# necklace1206ledfinal1.net
KiCad netlist of a schematic drawn in EAGLE
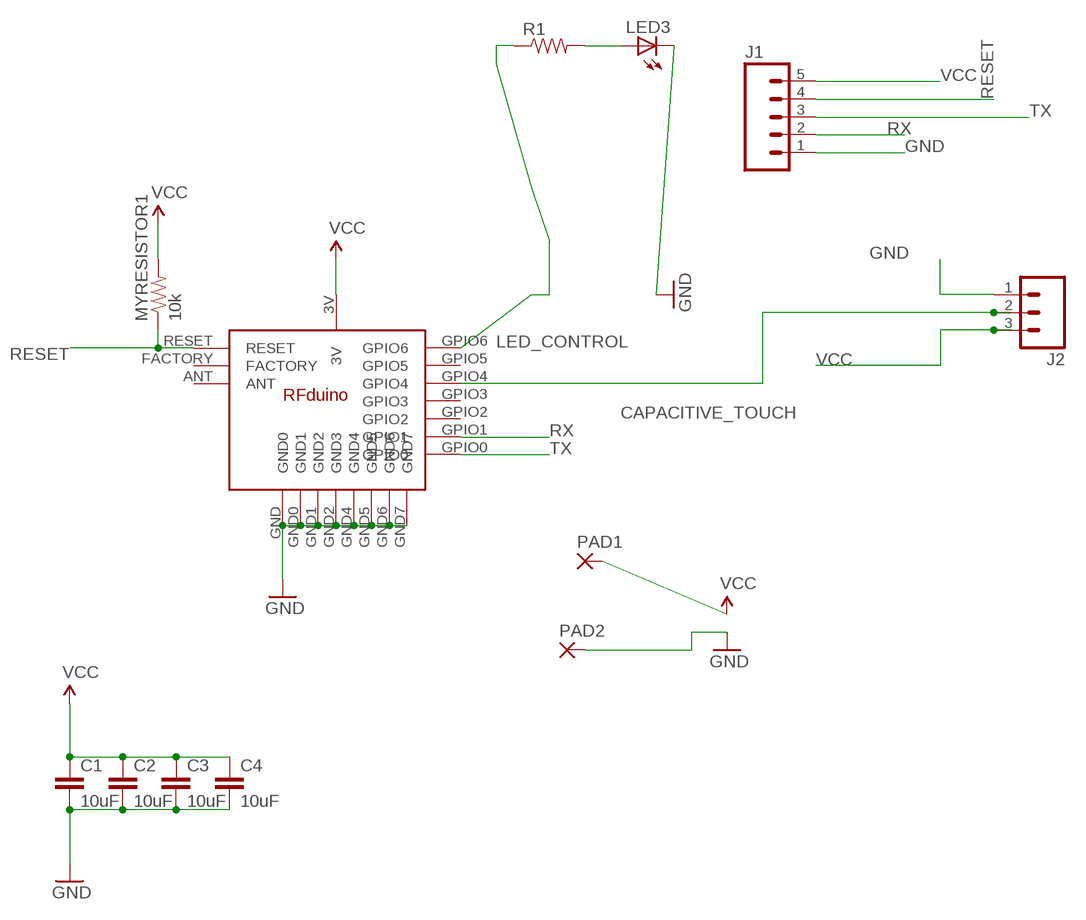
[diagram p0: schematic, sheet 1]

(export (version "E")
  (design (tool "Eeschema 10.0.6"))
  (components
    (comp (ref "C1")
      (value "10uF")
      (footprint "eagle-import:0603-CAP")
      (libsource (lib "eagle-import") (part "CAP0603-CAP"))
    )
    (comp (ref "C2")
      (value "10uF")
      (footprint "eagle-import:0603-CAP")
      (libsource (lib "eagle-import") (part "CAP0603-CAP"))
    )
    (comp (ref "C3")
      (value "10uF")
      (footprint "eagle-import:0603-CAP")
      (libsource (lib "eagle-import") (part "CAP0603-CAP"))
    )
    (comp (ref "C4")
      (value "10uF")
      (footprint "eagle-import:0603-CAP")
      (libsource (lib "eagle-import") (part "CAP0603-CAP"))
    )
    (comp (ref "J1")
      (value "M05PTH_LONGPADS")
      (footprint "eagle-import:1X05_LONGPADS")
      (libsource (lib "eagle-import") (part "M05PTH_LONGPADS"))
    )
    (comp (ref "J2")
      (value "M03LOCK_LONGPADS")
      (footprint "eagle-import:1X03_LOCK_LONGPADS")
      (libsource (lib "eagle-import") (part "M03LOCK_LONGPADS"))
    )
    (comp (ref "LED3")
      (value "LEDSMT1206")
      (footprint "eagle-import:1206")
      (libsource (lib "eagle-import") (part "LEDSMT1206"))
    )
    (comp (ref "MYRESISTOR1")
      (value "10k")
      (footprint "eagle-import:0603-RES")
      (libsource (lib "eagle-import") (part "RESISTOR0603-RES"))
    )
    (comp (ref "PAD1")
      (value "3,81/1,4")
      (footprint "eagle-import:3,81_1,4")
      (libsource (lib "eagle-import") (part "3,81/1,4"))
    )
    (comp (ref "PAD2")
      (value "3,81/1,4")
      (footprint "eagle-import:3,81_1,4")
      (libsource (lib "eagle-import") (part "3,81/1,4"))
    )
    (comp (ref "R1")
      (value "RESISTOR0603")
      (footprint "eagle-import:0603-RES")
      (libsource (lib "eagle-import") (part "RESISTOR0603"))
    )
    (comp (ref "U$2")
      (value "RFDUINO")
      (footprint "eagle-import:RFDUINO")
      (libsource (lib "eagle-import") (part "RFDUINO"))
    )
  )
  (nets
    (net (code "1") (name "/CAPACITIVE_TOUCH") (class "Default")
      (node (ref "J2") (pin "2") (pinfunction "2_2") (pintype "passive"))
      (node (ref "U$2") (pin "GPIO4") (pinfunction "GPIO4_GPIO4") (pintype "bidirectional"))
    )
    (net (code "2") (name "/LED_CONTROL") (class "Default")
      (node (ref "R1") (pin "1") (pinfunction "1_1") (pintype "passive"))
      (node (ref "U$2") (pin "GPIO6") (pinfunction "GPIO6_GPIO6") (pintype "bidirectional"))
    )
    (net (code "3") (name "/RESET") (class "Default")
      (node (ref "J1") (pin "4") (pinfunction "4_4") (pintype "passive"))
      (node (ref "MYRESISTOR1") (pin "1") (pinfunction "1_1") (pintype "passive"))
      (node (ref "U$2") (pin "RESET") (pinfunction "RESET_RESET") (pintype "bidirectional"))
    )
    (net (code "4") (name "/RX") (class "Default")
      (node (ref "J1") (pin "2") (pinfunction "2_2") (pintype "passive"))
      (node (ref "U$2") (pin "GPIO1") (pinfunction "GPIO1_GPIO1") (pintype "bidirectional"))
    )
    (net (code "5") (name "/TX") (class "Default")
      (node (ref "J1") (pin "3") (pinfunction "3_3") (pintype "passive"))
      (node (ref "U$2") (pin "GPIO0") (pinfunction "GPIO0_GPIO0") (pintype "bidirectional"))
    )
    (net (code "6") (name "GND") (class "Default")
      (node (ref "C1") (pin "2") (pinfunction "2_2") (pintype "passive"))
      (node (ref "C2") (pin "2") (pinfunction "2_2") (pintype "passive"))
      (node (ref "C3") (pin "2") (pinfunction "2_2") (pintype "passive"))
      (node (ref "C4") (pin "2") (pinfunction "2_2") (pintype "passive"))
      (node (ref "J1") (pin "1") (pinfunction "1_1") (pintype "passive"))
      (node (ref "J2") (pin "1") (pinfunction "1_1") (pintype "passive"))
      (node (ref "LED3") (pin "C") (pinfunction "C_C") (pintype "passive"))
      (node (ref "PAD2") (pin "1") (pinfunction "P_1") (pintype "passive"))
      (node (ref "U$2") (pin "GND") (pinfunction "GND0_GND") (pintype "bidirectional"))
      (node (ref "U$2") (pin "GND0") (pinfunction "GND1_GND0") (pintype "bidirectional"))
      (node (ref "U$2") (pin "GND1") (pinfunction "GND2_GND1") (pintype "bidirectional"))
      (node (ref "U$2") (pin "GND2") (pinfunction "GND3_GND2") (pintype "bidirectional"))
      (node (ref "U$2") (pin "GND4") (pinfunction "GND4_GND4") (pintype "bidirectional"))
      (node (ref "U$2") (pin "GND5") (pinfunction "GND5_GND5") (pintype "bidirectional"))
      (node (ref "U$2") (pin "GND6") (pinfunction "GND6_GND6") (pintype "bidirectional"))
      (node (ref "U$2") (pin "GND7") (pinfunction "GND7_GND7") (pintype "bidirectional"))
    )
    (net (code "7") (name "Net-(LED3-PadA)") (class "Default")
      (node (ref "LED3") (pin "A") (pinfunction "A_A") (pintype "passive"))
      (node (ref "R1") (pin "2") (pinfunction "2_2") (pintype "passive"))
    )
    (net (code "8") (name "VCC") (class "Default")
      (node (ref "C1") (pin "1") (pinfunction "1_1") (pintype "passive"))
      (node (ref "C2") (pin "1") (pinfunction "1_1") (pintype "passive"))
      (node (ref "C3") (pin "1") (pinfunction "1_1") (pintype "passive"))
      (node (ref "C4") (pin "1") (pinfunction "1_1") (pintype "passive"))
      (node (ref "J1") (pin "5") (pinfunction "5_5") (pintype "passive"))
      (node (ref "J2") (pin "3") (pinfunction "3_3") (pintype "passive"))
      (node (ref "MYRESISTOR1") (pin "2") (pinfunction "2_2") (pintype "passive"))
      (node (ref "PAD1") (pin "1") (pinfunction "P_1") (pintype "passive"))
      (node (ref "U$2") (pin "3V") (pinfunction "3V_3V") (pintype "bidirectional"))
    )
    (net (code "9") (name "unconnected-(U$2-PadANT)") (class "Default")
      (node (ref "U$2") (pin "ANT") (pinfunction "ANT_ANT") (pintype "bidirectional"))
    )
    (net (code "10") (name "unconnected-(U$2-PadFACTORY)") (class "Default")
      (node (ref "U$2") (pin "FACTORY") (pinfunction "FACTORY_FACTORY") (pintype "bidirectional"))
    )
    (net (code "11") (name "unconnected-(U$2-PadGPIO2)") (class "Default")
      (node (ref "U$2") (pin "GPIO2") (pinfunction "GPIO2_GPIO2") (pintype "bidirectional"))
    )
    (net (code "12") (name "unconnected-(U$2-PadGPIO3)") (class "Default")
      (node (ref "U$2") (pin "GPIO3") (pinfunction "GPIO3_GPIO3") (pintype "bidirectional"))
    )
    (net (code "13") (name "unconnected-(U$2-PadGPIO5)") (class "Default")
      (node (ref "U$2") (pin "GPIO5") (pinfunction "GPIO5_GPIO5") (pintype "bidirectional"))
    )
  )
)
